# USBtoUART.net
KiCad netlist of a schematic drawn in Altium Designer
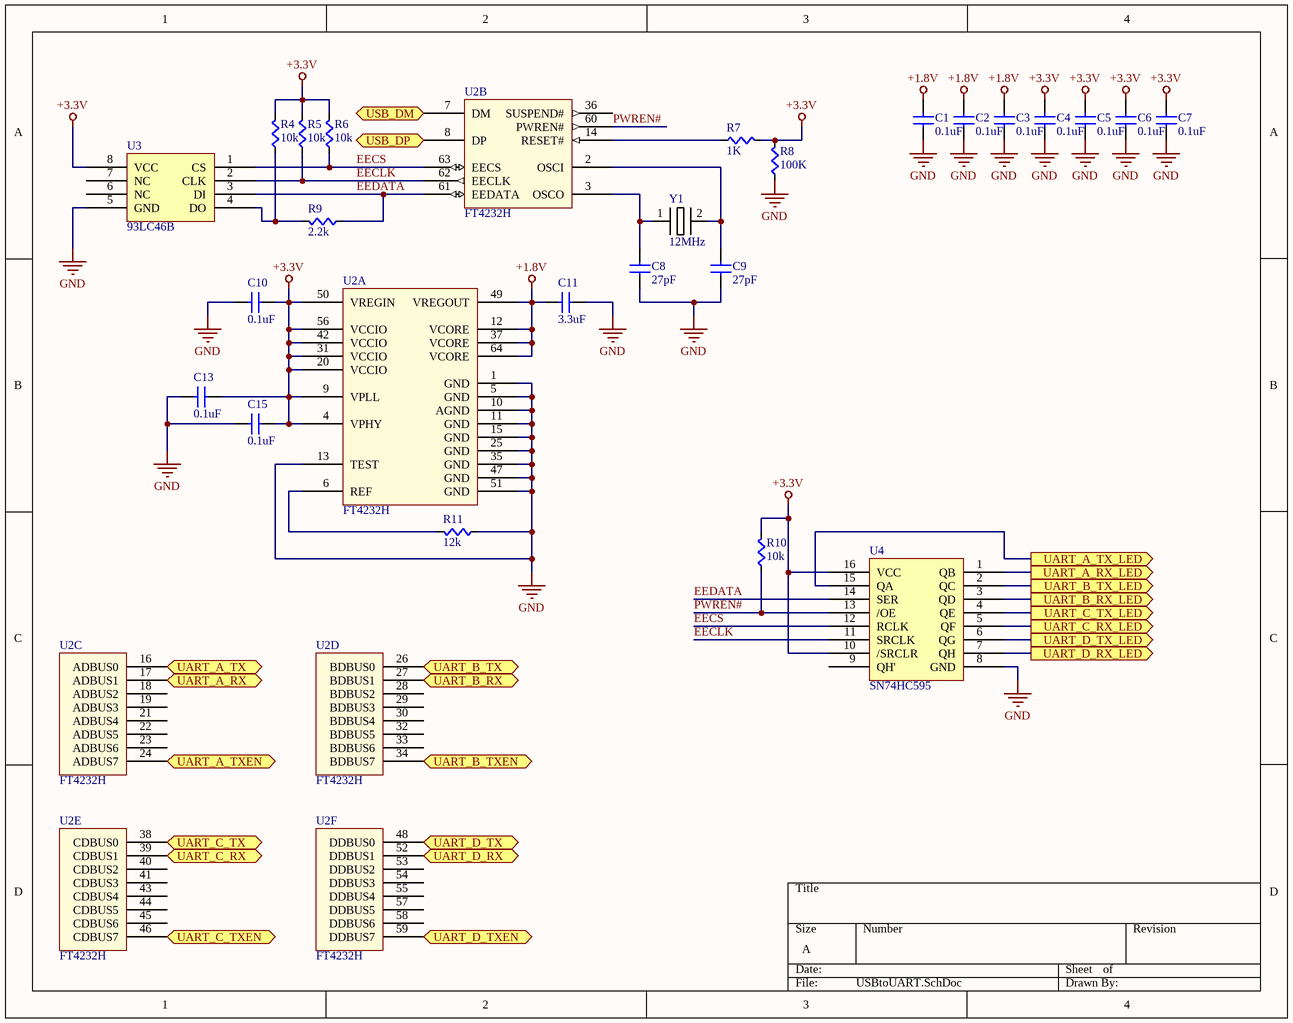
[diagram p0: USBtoUART.SchDoc]

(export (version "E")
  (design (tool "Eeschema 10.0.6"))
  (components
    (comp (ref "C1")
      (value "0.1uF")
      (footprint "CAPC0603")
      (description "CAP CER 0.1UF 50V X7R 0603")
      (fields (field (name "Comment") "Cap"))
      (libsource (lib "Passives") (part "Cap"))
    )
    (comp (ref "C2")
      (value "0.1uF")
      (footprint "CAPC0603")
      (description "CAP CER 0.1UF 50V X7R 0603")
      (fields (field (name "Comment") "Cap"))
      (libsource (lib "Passives") (part "Cap"))
    )
    (comp (ref "C3")
      (value "0.1uF")
      (footprint "CAPC0603")
      (description "CAP CER 0.1UF 50V X7R 0603")
      (fields (field (name "Comment") "Cap"))
      (libsource (lib "Passives") (part "Cap"))
    )
    (comp (ref "C4")
      (value "0.1uF")
      (footprint "CAPC0603")
      (description "CAP CER 0.1UF 50V X7R 0603")
      (fields (field (name "Comment") "Cap"))
      (libsource (lib "Passives") (part "Cap"))
    )
    (comp (ref "C5")
      (value "0.1uF")
      (footprint "CAPC0603")
      (description "CAP CER 0.1UF 50V X7R 0603")
      (fields (field (name "Comment") "Cap"))
      (libsource (lib "Passives") (part "Cap"))
    )
    (comp (ref "C6")
      (value "0.1uF")
      (footprint "CAPC0603")
      (description "CAP CER 0.1UF 50V X7R 0603")
      (fields (field (name "Comment") "Cap"))
      (libsource (lib "Passives") (part "Cap"))
    )
    (comp (ref "C7")
      (value "0.1uF")
      (footprint "CAPC0603")
      (description "CAP CER 0.1UF 50V X7R 0603")
      (fields (field (name "Comment") "Cap"))
      (libsource (lib "Passives") (part "Cap"))
    )
    (comp (ref "C8")
      (value "27pF")
      (footprint "CAPC0603")
      (description "CAP CER 27PF 50V NP0 0603")
      (fields (field (name "Comment") "Cap"))
      (libsource (lib "Passives") (part "Cap"))
    )
    (comp (ref "C9")
      (value "27pF")
      (footprint "CAPC0603")
      (description "CAP CER 27PF 50V NP0 0603")
      (fields (field (name "Comment") "Cap"))
      (libsource (lib "Passives") (part "Cap"))
    )
    (comp (ref "C10")
      (value "0.1uF")
      (footprint "CAPC0603")
      (description "CAP CER 0.1UF 50V X7R 0603")
      (fields (field (name "Comment") "Cap"))
      (libsource (lib "Passives") (part "Cap"))
    )
    (comp (ref "C11")
      (value "3.3uF")
      (footprint "CAPC0603")
      (description "CAP CER 3.3UF 16V X5R 0603")
      (fields (field (name "Comment") "Cap"))
      (libsource (lib "Passives") (part "Cap"))
    )
    (comp (ref "C13")
      (value "0.1uF")
      (footprint "Passives:CAPC0603")
      (description "CAP CER 0.1UF 50V X7R 0603")
      (fields (field (name "Comment") "Cap"))
      (libsource (lib "SubjuGator8") (part "Cap"))
    )
    (comp (ref "C15")
      (value "0.1uF")
      (footprint "Passives:CAPC0603")
      (description "CAP CER 0.1UF 50V X7R 0603")
      (fields (field (name "Comment") "Cap"))
      (libsource (lib "SubjuGator8") (part "Cap"))
    )
    (comp (ref "R4")
      (value "10k")
      (footprint "RES0603")
      (description "RES SMD 10K OHM 1% 1/10W 0603")
      (fields (field (name "Comment") "Res"))
      (libsource (lib "Passives") (part "Res"))
    )
    (comp (ref "R5")
      (value "10k")
      (footprint "RES0603")
      (description "RES SMD 10K OHM 1% 1/10W 0603")
      (fields (field (name "Comment") "Res"))
      (libsource (lib "Passives") (part "Res"))
    )
    (comp (ref "R6")
      (value "10k")
      (footprint "RES0603")
      (description "RES SMD 10K OHM 1% 1/10W 0603")
      (fields (field (name "Comment") "Res"))
      (libsource (lib "Passives") (part "Res"))
    )
    (comp (ref "R7")
      (value "1K")
      (footprint "RES0603")
      (description "RES SMD 1K OHM 1% 1/10W 0603")
      (fields (field (name "Comment") "Res"))
      (libsource (lib "Passives") (part "Res"))
    )
    (comp (ref "R8")
      (value "100K")
      (footprint "RES0603")
      (description "RES SMD 100K OHM 1% 1/10W 0603")
      (fields (field (name "Comment") "Res"))
      (libsource (lib "Passives") (part "Res"))
    )
    (comp (ref "R9")
      (value "2.2k")
      (footprint "RES0603")
      (description "RES SMD 2.2K OHM 1% 1/10W 0603")
      (fields (field (name "Comment") "Res"))
      (libsource (lib "Passives") (part "Res"))
    )
    (comp (ref "R10")
      (value "10k")
      (footprint "RES0603")
      (description "RES SMD 10K OHM 1% 1/10W 0603")
      (fields (field (name "Comment") "Res"))
      (libsource (lib "Passives") (part "Res"))
    )
    (comp (ref "R11")
      (value "12k")
      (footprint "RES0603")
      (description "RES SMD 12K OHM 1% 1/10W 0603")
      (fields (field (name "Comment") "Res"))
      (libsource (lib "Passives") (part "Res"))
    )
    (comp (ref "U2")
      (value "FT4232H")
      (footprint "FT4232HL")
      (description "IC USB HS QUAD UART/SYNC 64-LQFP")
      (libsource (lib "ICs") (part "FT4232H"))
    )
    (comp (ref "U3")
      (value "93LC46B")
      (footprint "SOIC-8pin")
      (description "IC EEPROM 1KBIT 2MHZ 8SOIC")
      (libsource (lib "ICs") (part "93LC46B"))
    )
    (comp (ref "U4")
      (value "SN74HC595")
      (footprint "TSSOP-16pin")
      (description "IC 8BIT SHIFT REGISTER 16-TSSOP")
      (libsource (lib "ICs") (part "SN74HC595"))
    )
    (comp (ref "Y1")
      (value "12MHz")
      (footprint "HC49/US")
      (description "CRYSTAL 12.0000MHZ 18PF SMD")
      (libsource (lib "ICs") (part "ABLS2-12.000MHZ-D4Y-T"))
    )
  )
  (nets
    (net (code "1") (name "+1.8V") (class "Default")
      (node (ref "C1") (pin "2") (pinfunction "B_2") (pintype "passive"))
      (node (ref "C11") (pin "1") (pinfunction "A_1") (pintype "passive"))
      (node (ref "C2") (pin "2") (pinfunction "B_2") (pintype "passive"))
      (node (ref "C3") (pin "2") (pinfunction "B_2") (pintype "passive"))
      (node (ref "U2") (pin "12") (pinfunction "VCORE_12") (pintype "power_in"))
      (node (ref "U2") (pin "37") (pinfunction "VCORE_37") (pintype "power_in"))
      (node (ref "U2") (pin "49") (pinfunction "VREGOUT_49") (pintype "power_in"))
      (node (ref "U2") (pin "64") (pinfunction "VCORE_64") (pintype "power_in"))
    )
    (net (code "2") (name "+3.3V") (class "Default")
      (node (ref "C10") (pin "2") (pinfunction "B_2") (pintype "passive"))
      (node (ref "C13") (pin "2") (pinfunction "B_2") (pintype "passive"))
      (node (ref "C15") (pin "1") (pinfunction "A_1") (pintype "passive"))
      (node (ref "C4") (pin "2") (pinfunction "B_2") (pintype "passive"))
      (node (ref "C5") (pin "2") (pinfunction "B_2") (pintype "passive"))
      (node (ref "C6") (pin "2") (pinfunction "B_2") (pintype "passive"))
      (node (ref "C7") (pin "2") (pinfunction "B_2") (pintype "passive"))
      (node (ref "R10") (pin "1") (pinfunction "A_1") (pintype "passive"))
      (node (ref "R4") (pin "1") (pinfunction "A_1") (pintype "passive"))
      (node (ref "R5") (pin "1") (pinfunction "A_1") (pintype "passive"))
      (node (ref "R6") (pin "1") (pinfunction "A_1") (pintype "passive"))
      (node (ref "R7") (pin "1") (pinfunction "A_1") (pintype "passive"))
      (node (ref "R8") (pin "1") (pinfunction "A_1") (pintype "passive"))
      (node (ref "U2") (pin "20") (pinfunction "VCCIO_20") (pintype "power_in"))
      (node (ref "U2") (pin "31") (pinfunction "VCCIO_31") (pintype "power_in"))
      (node (ref "U2") (pin "4") (pinfunction "VPHY_4") (pintype "power_in"))
      (node (ref "U2") (pin "42") (pinfunction "VCCIO_42") (pintype "power_in"))
      (node (ref "U2") (pin "50") (pinfunction "VREGIN_50") (pintype "power_in"))
      (node (ref "U2") (pin "56") (pinfunction "VCCIO_56") (pintype "power_in"))
      (node (ref "U2") (pin "9") (pinfunction "VPLL_9") (pintype "power_in"))
      (node (ref "U3") (pin "8") (pinfunction "VCC_8") (pintype "passive"))
      (node (ref "U4") (pin "10") (pinfunction "/SRCLR_10") (pintype "passive"))
      (node (ref "U4") (pin "16") (pinfunction "VCC_16") (pintype "passive"))
    )
    (net (code "3") (name "/EECLK") (class "Default")
      (node (ref "R5") (pin "2") (pinfunction "B_2") (pintype "passive"))
      (node (ref "U2") (pin "62") (pinfunction "EECLK_62") (pintype "output"))
      (node (ref "U3") (pin "2") (pinfunction "CLK_2") (pintype "passive"))
      (node (ref "U4") (pin "11") (pinfunction "SRCLK_11") (pintype "passive"))
    )
    (net (code "4") (name "/EECS") (class "Default")
      (node (ref "R6") (pin "2") (pinfunction "B_2") (pintype "passive"))
      (node (ref "U2") (pin "63") (pinfunction "EECS_63") (pintype "bidirectional"))
      (node (ref "U3") (pin "1") (pinfunction "CS_1") (pintype "passive"))
      (node (ref "U4") (pin "12") (pinfunction "RCLK_12") (pintype "passive"))
    )
    (net (code "5") (name "/EEDATA") (class "Default")
      (node (ref "R9") (pin "2") (pinfunction "B_2") (pintype "passive"))
      (node (ref "U2") (pin "61") (pinfunction "EEDATA_61") (pintype "bidirectional"))
      (node (ref "U3") (pin "3") (pinfunction "DI_3") (pintype "passive"))
      (node (ref "U4") (pin "14") (pinfunction "SER_14") (pintype "passive"))
    )
    (net (code "6") (name "/PWREN#") (class "Default")
      (node (ref "R10") (pin "2") (pinfunction "B_2") (pintype "passive"))
      (node (ref "U2") (pin "60") (pinfunction "PWREN#_60") (pintype "output"))
      (node (ref "U4") (pin "13") (pinfunction "/OE_13") (pintype "passive"))
    )
    (net (code "7") (name "/UART_A_RX") (class "Default")
      (node (ref "U2") (pin "17") (pinfunction "ADBUS1_17") (pintype "passive"))
    )
    (net (code "8") (name "/UART_A_RX_LED") (class "Default")
      (node (ref "U4") (pin "1") (pinfunction "QB_1") (pintype "passive"))
    )
    (net (code "9") (name "/UART_A_TX") (class "Default")
      (node (ref "U2") (pin "16") (pinfunction "ADBUS0_16") (pintype "passive"))
    )
    (net (code "10") (name "/UART_A_TXEN") (class "Default")
      (node (ref "U2") (pin "24") (pinfunction "ADBUS7_24") (pintype "passive"))
    )
    (net (code "11") (name "/UART_A_TX_LED") (class "Default")
      (node (ref "U4") (pin "15") (pinfunction "QA_15") (pintype "passive"))
    )
    (net (code "12") (name "/UART_B_RX") (class "Default")
      (node (ref "U2") (pin "27") (pinfunction "BDBUS1_27") (pintype "passive"))
    )
    (net (code "13") (name "/UART_B_RX_LED") (class "Default")
      (node (ref "U4") (pin "3") (pinfunction "QD_3") (pintype "passive"))
    )
    (net (code "14") (name "/UART_B_TX") (class "Default")
      (node (ref "U2") (pin "26") (pinfunction "BDBUS0_26") (pintype "passive"))
    )
    (net (code "15") (name "/UART_B_TXEN") (class "Default")
      (node (ref "U2") (pin "34") (pinfunction "BDBUS7_34") (pintype "passive"))
    )
    (net (code "16") (name "/UART_B_TX_LED") (class "Default")
      (node (ref "U4") (pin "2") (pinfunction "QC_2") (pintype "passive"))
    )
    (net (code "17") (name "/UART_C_RX") (class "Default")
      (node (ref "U2") (pin "39") (pinfunction "CDBUS1_39") (pintype "passive"))
    )
    (net (code "18") (name "/UART_C_RX_LED") (class "Default")
      (node (ref "U4") (pin "5") (pinfunction "QF_5") (pintype "passive"))
    )
    (net (code "19") (name "/UART_C_TX") (class "Default")
      (node (ref "U2") (pin "38") (pinfunction "CDBUS0_38") (pintype "passive"))
    )
    (net (code "20") (name "/UART_C_TXEN") (class "Default")
      (node (ref "U2") (pin "46") (pinfunction "CDBUS7_46") (pintype "passive"))
    )
    (net (code "21") (name "/UART_C_TX_LED") (class "Default")
      (node (ref "U4") (pin "4") (pinfunction "QE_4") (pintype "passive"))
    )
    (net (code "22") (name "/UART_D_RX") (class "Default")
      (node (ref "U2") (pin "52") (pinfunction "DDBUS1_52") (pintype "passive"))
    )
    (net (code "23") (name "/UART_D_RX_LED") (class "Default")
      (node (ref "U4") (pin "7") (pinfunction "QH_7") (pintype "passive"))
    )
    (net (code "24") (name "/UART_D_TX") (class "Default")
      (node (ref "U2") (pin "48") (pinfunction "DDBUS0_48") (pintype "passive"))
    )
    (net (code "25") (name "/UART_D_TXEN") (class "Default")
      (node (ref "U2") (pin "59") (pinfunction "DDBUS7_59") (pintype "passive"))
    )
    (net (code "26") (name "/UART_D_TX_LED") (class "Default")
      (node (ref "U4") (pin "6") (pinfunction "QG_6") (pintype "passive"))
    )
    (net (code "27") (name "/USB_DM") (class "Default")
      (node (ref "U2") (pin "7") (pinfunction "DM_7") (pintype "passive"))
    )
    (net (code "28") (name "/USB_DP") (class "Default")
      (node (ref "U2") (pin "8") (pinfunction "DP_8") (pintype "passive"))
    )
    (net (code "29") (name "GND") (class "Default")
      (node (ref "C1") (pin "1") (pinfunction "A_1") (pintype "passive"))
      (node (ref "C10") (pin "1") (pinfunction "A_1") (pintype "passive"))
      (node (ref "C11") (pin "2") (pinfunction "B_2") (pintype "passive"))
      (node (ref "C13") (pin "1") (pinfunction "A_1") (pintype "passive"))
      (node (ref "C15") (pin "2") (pinfunction "B_2") (pintype "passive"))
      (node (ref "C2") (pin "1") (pinfunction "A_1") (pintype "passive"))
      (node (ref "C3") (pin "1") (pinfunction "A_1") (pintype "passive"))
      (node (ref "C4") (pin "1") (pinfunction "A_1") (pintype "passive"))
      (node (ref "C5") (pin "1") (pinfunction "A_1") (pintype "passive"))
      (node (ref "C6") (pin "1") (pinfunction "A_1") (pintype "passive"))
      (node (ref "C7") (pin "1") (pinfunction "A_1") (pintype "passive"))
      (node (ref "C8") (pin "2") (pinfunction "B_2") (pintype "passive"))
      (node (ref "C9") (pin "2") (pinfunction "B_2") (pintype "passive"))
      (node (ref "R11") (pin "2") (pinfunction "B_2") (pintype "passive"))
      (node (ref "R8") (pin "2") (pinfunction "B_2") (pintype "passive"))
      (node (ref "U2") (pin "1") (pinfunction "GND_1") (pintype "power_in"))
      (node (ref "U2") (pin "10") (pinfunction "AGND_10") (pintype "power_in"))
      (node (ref "U2") (pin "11") (pinfunction "GND_11") (pintype "power_in"))
      (node (ref "U2") (pin "13") (pinfunction "TEST_13") (pintype "passive"))
      (node (ref "U2") (pin "15") (pinfunction "GND_15") (pintype "power_in"))
      (node (ref "U2") (pin "25") (pinfunction "GND_25") (pintype "power_in"))
      (node (ref "U2") (pin "35") (pinfunction "GND_35") (pintype "power_in"))
      (node (ref "U2") (pin "47") (pinfunction "GND_47") (pintype "power_in"))
      (node (ref "U2") (pin "5") (pinfunction "GND_5") (pintype "power_in"))
      (node (ref "U2") (pin "51") (pinfunction "GND_51") (pintype "power_in"))
      (node (ref "U3") (pin "5") (pinfunction "GND_5") (pintype "passive"))
      (node (ref "U4") (pin "8") (pinfunction "GND_8") (pintype "passive"))
    )
    (net (code "30") (name "Net-(C8-A)") (class "Default")
      (node (ref "C8") (pin "1") (pinfunction "A_1") (pintype "passive"))
      (node (ref "U2") (pin "3") (pinfunction "OSCO_3") (pintype "passive"))
      (node (ref "Y1") (pin "1") (pinfunction "1_1") (pintype "passive"))
    )
    (net (code "31") (name "Net-(C9-A)") (class "Default")
      (node (ref "C9") (pin "1") (pinfunction "A_1") (pintype "passive"))
      (node (ref "U2") (pin "2") (pinfunction "OSCI_2") (pintype "passive"))
      (node (ref "Y1") (pin "2") (pinfunction "2_2") (pintype "passive"))
    )
    (net (code "32") (name "Net-(R4-B)") (class "Default")
      (node (ref "R4") (pin "2") (pinfunction "B_2") (pintype "passive"))
      (node (ref "R9") (pin "1") (pinfunction "A_1") (pintype "passive"))
      (node (ref "U3") (pin "4") (pinfunction "DO_4") (pintype "passive"))
    )
    (net (code "33") (name "Net-(R7-B)") (class "Default")
      (node (ref "R7") (pin "2") (pinfunction "B_2") (pintype "passive"))
      (node (ref "U2") (pin "14") (pinfunction "RESET#_14") (pintype "input"))
    )
    (net (code "34") (name "Net-(R11-A)") (class "Default")
      (node (ref "R11") (pin "1") (pinfunction "A_1") (pintype "passive"))
      (node (ref "U2") (pin "6") (pinfunction "REF_6") (pintype "passive"))
    )
    (net (code "35") (name "unconnected-(U2B-SUSPEND#-Pad36)") (class "Default")
      (node (ref "U2") (pin "36") (pinfunction "SUSPEND#_36") (pintype "output"))
    )
    (net (code "36") (name "unconnected-(U2C-ADBUS2-Pad18)") (class "Default")
      (node (ref "U2") (pin "18") (pinfunction "ADBUS2_18") (pintype "passive"))
    )
    (net (code "37") (name "unconnected-(U2C-ADBUS3-Pad19)") (class "Default")
      (node (ref "U2") (pin "19") (pinfunction "ADBUS3_19") (pintype "passive"))
    )
    (net (code "38") (name "unconnected-(U2C-ADBUS4-Pad21)") (class "Default")
      (node (ref "U2") (pin "21") (pinfunction "ADBUS4_21") (pintype "passive"))
    )
    (net (code "39") (name "unconnected-(U2C-ADBUS5-Pad22)") (class "Default")
      (node (ref "U2") (pin "22") (pinfunction "ADBUS5_22") (pintype "passive"))
    )
    (net (code "40") (name "unconnected-(U2C-ADBUS6-Pad23)") (class "Default")
      (node (ref "U2") (pin "23") (pinfunction "ADBUS6_23") (pintype "passive"))
    )
    (net (code "41") (name "unconnected-(U2D-BDBUS2-Pad28)") (class "Default")
      (node (ref "U2") (pin "28") (pinfunction "BDBUS2_28") (pintype "passive"))
    )
    (net (code "42") (name "unconnected-(U2D-BDBUS3-Pad29)") (class "Default")
      (node (ref "U2") (pin "29") (pinfunction "BDBUS3_29") (pintype "passive"))
    )
    (net (code "43") (name "unconnected-(U2D-BDBUS4-Pad30)") (class "Default")
      (node (ref "U2") (pin "30") (pinfunction "BDBUS4_30") (pintype "passive"))
    )
    (net (code "44") (name "unconnected-(U2D-BDBUS5-Pad32)") (class "Default")
      (node (ref "U2") (pin "32") (pinfunction "BDBUS5_32") (pintype "passive"))
    )
    (net (code "45") (name "unconnected-(U2D-BDBUS6-Pad33)") (class "Default")
      (node (ref "U2") (pin "33") (pinfunction "BDBUS6_33") (pintype "passive"))
    )
    (net (code "46") (name "unconnected-(U2E-CDBUS2-Pad40)") (class "Default")
      (node (ref "U2") (pin "40") (pinfunction "CDBUS2_40") (pintype "passive"))
    )
    (net (code "47") (name "unconnected-(U2E-CDBUS3-Pad41)") (class "Default")
      (node (ref "U2") (pin "41") (pinfunction "CDBUS3_41") (pintype "passive"))
    )
    (net (code "48") (name "unconnected-(U2E-CDBUS4-Pad43)") (class "Default")
      (node (ref "U2") (pin "43") (pinfunction "CDBUS4_43") (pintype "passive"))
    )
    (net (code "49") (name "unconnected-(U2E-CDBUS5-Pad44)") (class "Default")
      (node (ref "U2") (pin "44") (pinfunction "CDBUS5_44") (pintype "passive"))
    )
    (net (code "50") (name "unconnected-(U2E-CDBUS6-Pad45)") (class "Default")
      (node (ref "U2") (pin "45") (pinfunction "CDBUS6_45") (pintype "passive"))
    )
    (net (code "51") (name "unconnected-(U2F-DDBUS2-Pad53)") (class "Default")
      (node (ref "U2") (pin "53") (pinfunction "DDBUS2_53") (pintype "passive"))
    )
    (net (code "52") (name "unconnected-(U2F-DDBUS3-Pad54)") (class "Default")
      (node (ref "U2") (pin "54") (pinfunction "DDBUS3_54") (pintype "passive"))
    )
    (net (code "53") (name "unconnected-(U2F-DDBUS4-Pad55)") (class "Default")
      (node (ref "U2") (pin "55") (pinfunction "DDBUS4_55") (pintype "passive"))
    )
    (net (code "54") (name "unconnected-(U2F-DDBUS5-Pad57)") (class "Default")
      (node (ref "U2") (pin "57") (pinfunction "DDBUS5_57") (pintype "passive"))
    )
    (net (code "55") (name "unconnected-(U2F-DDBUS6-Pad58)") (class "Default")
      (node (ref "U2") (pin "58") (pinfunction "DDBUS6_58") (pintype "passive"))
    )
    (net (code "56") (name "unconnected-(U3-NC-Pad6)") (class "Default")
      (node (ref "U3") (pin "6") (pinfunction "NC_6") (pintype "passive"))
    )
    (net (code "57") (name "unconnected-(U3-NC-Pad7)") (class "Default")
      (node (ref "U3") (pin "7") (pinfunction "NC_7") (pintype "passive"))
    )
    (net (code "58") (name "unconnected-(U4-QH'-Pad9)") (class "Default")
      (node (ref "U4") (pin "9") (pinfunction "QH'_9") (pintype "passive"))
    )
  )
)
